# EyeSpark.net
KiCad netlist of a schematic drawn in EAGLE
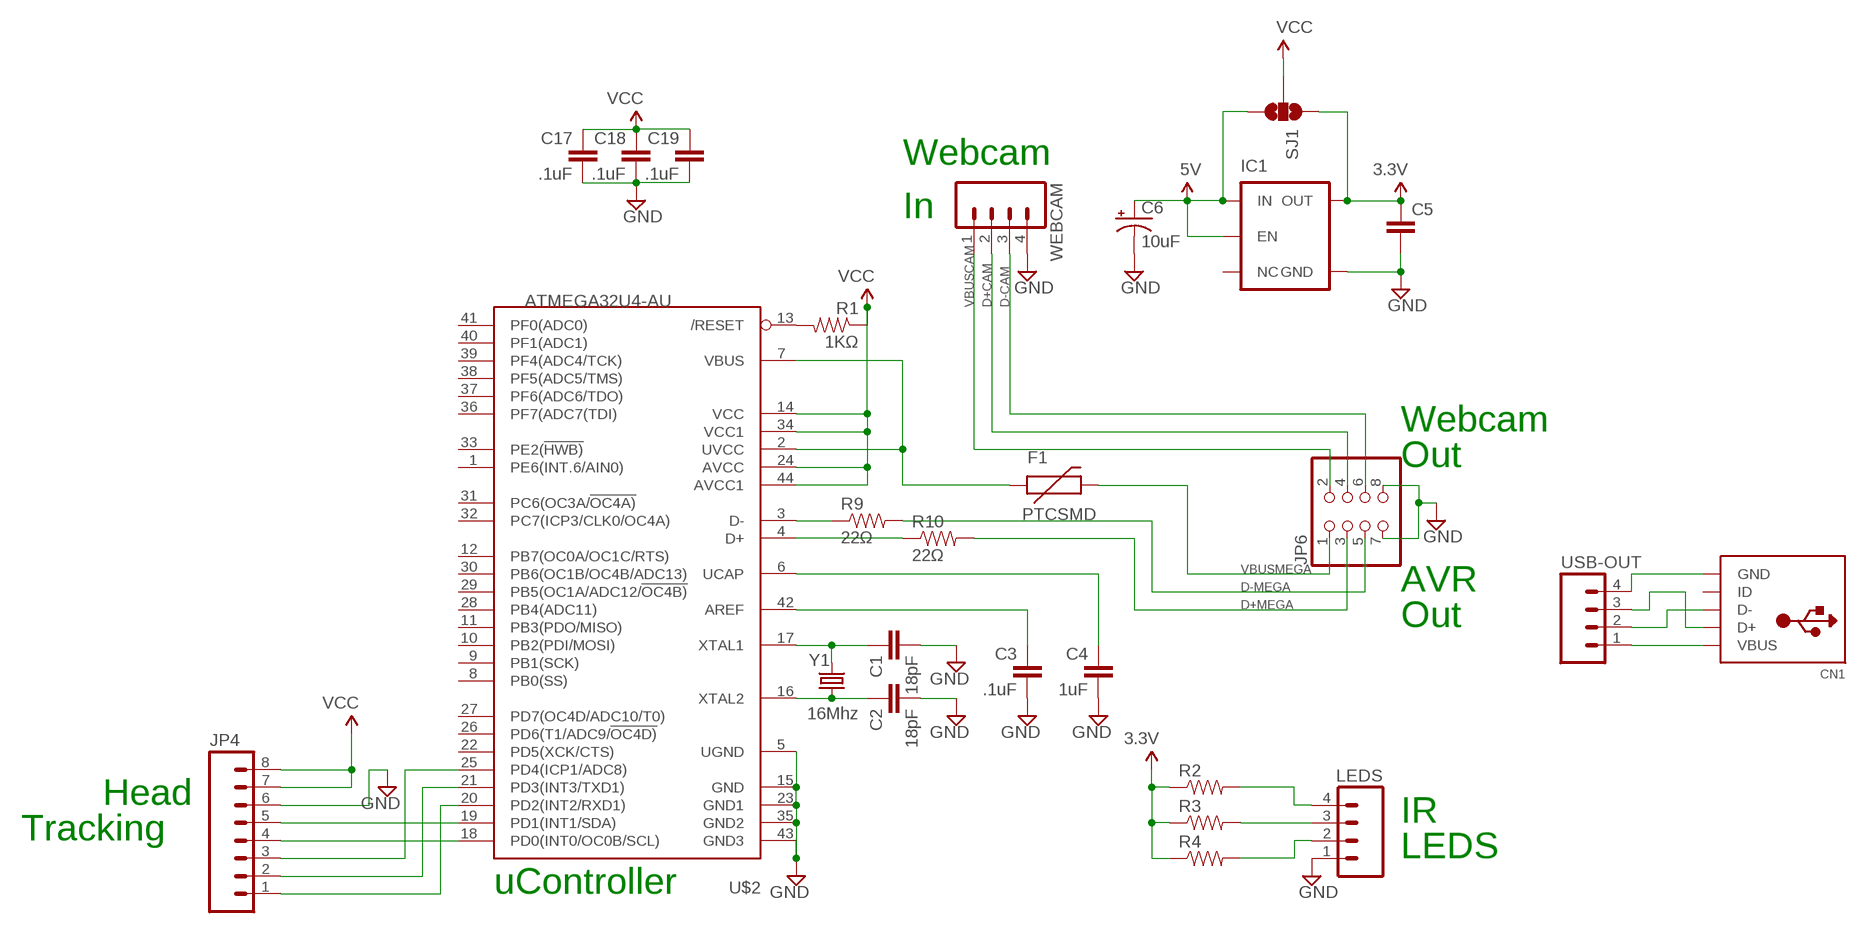
[diagram p0: schematic, sheet 1]

(export (version "E")
  (design (tool "Eeschema 10.0.6"))
  (components
    (comp (ref "C1")
      (value "18pF")
      (footprint "eagle-import:0805")
      (libsource (lib "eagle-import") (part "CAP0805"))
    )
    (comp (ref "C2")
      (value "18pF")
      (footprint "eagle-import:0805")
      (libsource (lib "eagle-import") (part "CAP0805"))
    )
    (comp (ref "C3")
      (value ".1uF")
      (footprint "eagle-import:0805")
      (libsource (lib "eagle-import") (part "CAP0805"))
    )
    (comp (ref "C4")
      (value "1uF")
      (footprint "eagle-import:0805")
      (libsource (lib "eagle-import") (part "CAP0805"))
    )
    (comp (ref "C5")
      (value "CAP0805")
      (footprint "eagle-import:0805")
      (libsource (lib "eagle-import") (part "CAP0805"))
    )
    (comp (ref "C6")
      (value "10uF")
      (footprint "eagle-import:EIA7343")
      (libsource (lib "eagle-import") (part "CAP_POL7343"))
    )
    (comp (ref "C17")
      (value ".1uF")
      (footprint "eagle-import:0805")
      (libsource (lib "eagle-import") (part "CAP0805"))
    )
    (comp (ref "C18")
      (value ".1uF")
      (footprint "eagle-import:0805")
      (libsource (lib "eagle-import") (part "CAP0805"))
    )
    (comp (ref "C19")
      (value ".1uF")
      (footprint "eagle-import:0805")
      (libsource (lib "eagle-import") (part "CAP0805"))
    )
    (comp (ref "CN1")
      (value "USBMINIB")
      (footprint "eagle-import:USB-MINIB")
      (libsource (lib "eagle-import") (part "USBMINIB"))
    )
    (comp (ref "F1")
      (value "PTCSMD")
      (footprint "eagle-import:PTC-1206")
      (libsource (lib "eagle-import") (part "PTCSMD"))
    )
    (comp (ref "IC1")
      (value "V_REG_TPS76433SOT23-5")
      (footprint "eagle-import:SOT23-5")
      (libsource (lib "eagle-import") (part "V_REG_TPS76433SOT23-5"))
    )
    (comp (ref "JP4")
      (value "M08LOCK")
      (footprint "eagle-import:1X08_LOCK")
      (libsource (lib "eagle-import") (part "M08LOCK"))
    )
    (comp (ref "JP6")
      (value "PINHD-2X4")
      (footprint "eagle-import:2X04")
      (libsource (lib "eagle-import") (part "PINHD-2X4"))
    )
    (comp (ref "LEDS")
      (value "M04PTH")
      (footprint "eagle-import:1X04")
      (libsource (lib "eagle-import") (part "M04PTH"))
    )
    (comp (ref "R1")
      (value "1KΩ")
      (footprint "eagle-import:0805")
      (libsource (lib "eagle-import") (part "RESISTOR0805-RES"))
    )
    (comp (ref "R2")
      (value "RESISTOR1206")
      (footprint "eagle-import:1206")
      (libsource (lib "eagle-import") (part "RESISTOR1206"))
    )
    (comp (ref "R3")
      (value "RESISTOR1206")
      (footprint "eagle-import:1206")
      (libsource (lib "eagle-import") (part "RESISTOR1206"))
    )
    (comp (ref "R4")
      (value "RESISTOR1206")
      (footprint "eagle-import:1206")
      (libsource (lib "eagle-import") (part "RESISTOR1206"))
    )
    (comp (ref "R9")
      (value "22Ω")
      (footprint "eagle-import:0805")
      (libsource (lib "eagle-import") (part "RESISTOR0805-RES"))
    )
    (comp (ref "R10")
      (value "22Ω")
      (footprint "eagle-import:0805")
      (libsource (lib "eagle-import") (part "RESISTOR0805-RES"))
    )
    (comp (ref "SJ1")
      (value "SOLDERJUMPER_2WAYT")
      (footprint "eagle-import:SJ_2")
      (libsource (lib "eagle-import") (part "SOLDERJUMPER_2WAYT"))
    )
    (comp (ref "U$2")
      (value "ATMEGA32U4-AU")
      (footprint "eagle-import:TQFP44")
      (libsource (lib "eagle-import") (part "ATMEGA32U4-AU"))
    )
    (comp (ref "USB-OUT")
      (value "M04PTH")
      (footprint "eagle-import:1X04")
      (libsource (lib "eagle-import") (part "M04PTH"))
    )
    (comp (ref "WEBCAM")
      (value "M04LOCK_LONGPADS")
      (footprint "eagle-import:1X04_LOCK_LONGPADS")
      (libsource (lib "eagle-import") (part "M04LOCK_LONGPADS"))
    )
    (comp (ref "Y1")
      (value "16Mhz")
      (footprint "eagle-import:CRYSTAL-SMD-5X3")
      (libsource (lib "eagle-import") (part "CRYSTAL5X3"))
    )
  )
  (nets
    (net (code "1") (name "/D+CAM") (class "Default")
      (node (ref "JP6") (pin "4") (pinfunction "4_4") (pintype "passive"))
      (node (ref "WEBCAM") (pin "2") (pinfunction "2_2") (pintype "passive"))
    )
    (net (code "2") (name "/D+MEGA") (class "Default")
      (node (ref "JP6") (pin "3") (pinfunction "3_3") (pintype "passive"))
      (node (ref "R10") (pin "2") (pinfunction "2_2") (pintype "passive"))
    )
    (net (code "3") (name "/D-CAM") (class "Default")
      (node (ref "JP6") (pin "6") (pinfunction "6_6") (pintype "passive"))
      (node (ref "WEBCAM") (pin "3") (pinfunction "3_3") (pintype "passive"))
    )
    (net (code "4") (name "/D-MEGA") (class "Default")
      (node (ref "JP6") (pin "5") (pinfunction "5_5") (pintype "passive"))
      (node (ref "R9") (pin "2") (pinfunction "2_2") (pintype "passive"))
    )
    (net (code "5") (name "/VBUSCAM") (class "Default")
      (node (ref "JP6") (pin "2") (pinfunction "2_2") (pintype "passive"))
      (node (ref "WEBCAM") (pin "1") (pinfunction "1_1") (pintype "passive"))
    )
    (net (code "6") (name "/VBUSMEGA") (class "Default")
      (node (ref "F1") (pin "2") (pinfunction "2_2") (pintype "bidirectional"))
      (node (ref "JP6") (pin "1") (pinfunction "1_1") (pintype "passive"))
    )
    (net (code "7") (name "3.3V") (class "Default")
      (node (ref "C5") (pin "1") (pinfunction "1_1") (pintype "passive"))
      (node (ref "IC1") (pin "5") (pinfunction "OUT_5") (pintype "passive"))
      (node (ref "R2") (pin "1") (pinfunction "1_1") (pintype "passive"))
      (node (ref "R3") (pin "1") (pinfunction "1_1") (pintype "passive"))
      (node (ref "R4") (pin "1") (pinfunction "1_1") (pintype "passive"))
      (node (ref "SJ1") (pin "1") (pinfunction "1_1") (pintype "passive"))
    )
    (net (code "8") (name "5V") (class "Default")
      (node (ref "C6") (pin "A") (pinfunction "+_A") (pintype "passive"))
      (node (ref "IC1") (pin "1") (pinfunction "IN_1") (pintype "input"))
      (node (ref "IC1") (pin "3") (pinfunction "EN_3") (pintype "input"))
      (node (ref "SJ1") (pin "3") (pinfunction "3_3") (pintype "passive"))
    )
    (net (code "9") (name "GND") (class "Default")
      (node (ref "C1") (pin "2") (pinfunction "2_2") (pintype "passive"))
      (node (ref "C17") (pin "2") (pinfunction "2_2") (pintype "passive"))
      (node (ref "C18") (pin "2") (pinfunction "2_2") (pintype "passive"))
      (node (ref "C19") (pin "2") (pinfunction "2_2") (pintype "passive"))
      (node (ref "C2") (pin "2") (pinfunction "2_2") (pintype "passive"))
      (node (ref "C3") (pin "2") (pinfunction "2_2") (pintype "passive"))
      (node (ref "C4") (pin "2") (pinfunction "2_2") (pintype "passive"))
      (node (ref "C5") (pin "2") (pinfunction "2_2") (pintype "passive"))
      (node (ref "C6") (pin "C") (pinfunction "-_C") (pintype "passive"))
      (node (ref "IC1") (pin "2") (pinfunction "GND_2") (pintype "input"))
      (node (ref "JP4") (pin "6") (pinfunction "6_6") (pintype "passive"))
      (node (ref "JP6") (pin "7") (pinfunction "7_7") (pintype "passive"))
      (node (ref "JP6") (pin "8") (pinfunction "8_8") (pintype "passive"))
      (node (ref "LEDS") (pin "1") (pinfunction "1_1") (pintype "passive"))
      (node (ref "U$2") (pin "15") (pinfunction "GND_15") (pintype "bidirectional"))
      (node (ref "U$2") (pin "23") (pinfunction "GND1_23") (pintype "bidirectional"))
      (node (ref "U$2") (pin "35") (pinfunction "GND2_35") (pintype "bidirectional"))
      (node (ref "U$2") (pin "43") (pinfunction "GND3_43") (pintype "bidirectional"))
      (node (ref "U$2") (pin "5") (pinfunction "UGND_5") (pintype "bidirectional"))
      (node (ref "WEBCAM") (pin "4") (pinfunction "4_4") (pintype "passive"))
    )
    (net (code "10") (name "Net-(CN1-PadD+)") (class "Default")
      (node (ref "CN1") (pin "D+") (pinfunction "D+_D+") (pintype "bidirectional"))
      (node (ref "USB-OUT") (pin "3") (pinfunction "3_3") (pintype "passive"))
    )
    (net (code "11") (name "Net-(CN1-PadD-)") (class "Default")
      (node (ref "CN1") (pin "D-") (pinfunction "D-_D-") (pintype "bidirectional"))
      (node (ref "USB-OUT") (pin "2") (pinfunction "2_2") (pintype "passive"))
    )
    (net (code "12") (name "Net-(CN1-PadGND)") (class "Default")
      (node (ref "CN1") (pin "GND") (pinfunction "GND_GND") (pintype "power_in"))
      (node (ref "USB-OUT") (pin "4") (pinfunction "4_4") (pintype "passive"))
    )
    (net (code "13") (name "Net-(CN1-PadVBUS)") (class "Default")
      (node (ref "CN1") (pin "VBUS") (pinfunction "VBUS_VBUS") (pintype "power_in"))
      (node (ref "USB-OUT") (pin "1") (pinfunction "1_1") (pintype "passive"))
    )
    (net (code "14") (name "Net-(LEDS-Pad2)") (class "Default")
      (node (ref "LEDS") (pin "2") (pinfunction "2_2") (pintype "passive"))
      (node (ref "R4") (pin "2") (pinfunction "2_2") (pintype "passive"))
    )
    (net (code "15") (name "Net-(LEDS-Pad3)") (class "Default")
      (node (ref "LEDS") (pin "3") (pinfunction "3_3") (pintype "passive"))
      (node (ref "R3") (pin "2") (pinfunction "2_2") (pintype "passive"))
    )
    (net (code "16") (name "Net-(LEDS-Pad4)") (class "Default")
      (node (ref "LEDS") (pin "4") (pinfunction "4_4") (pintype "passive"))
      (node (ref "R2") (pin "2") (pinfunction "2_2") (pintype "passive"))
    )
    (net (code "17") (name "Net-(U$2-AREF)") (class "Default")
      (node (ref "C3") (pin "1") (pinfunction "1_1") (pintype "passive"))
      (node (ref "U$2") (pin "42") (pinfunction "AREF_42") (pintype "bidirectional"))
    )
    (net (code "18") (name "Net-(U$2-D+)") (class "Default")
      (node (ref "R10") (pin "1") (pinfunction "1_1") (pintype "passive"))
      (node (ref "U$2") (pin "4") (pinfunction "D+_4") (pintype "bidirectional"))
    )
    (net (code "19") (name "Net-(U$2-D-)") (class "Default")
      (node (ref "R9") (pin "1") (pinfunction "1_1") (pintype "passive"))
      (node (ref "U$2") (pin "3") (pinfunction "D-_3") (pintype "bidirectional"))
    )
    (net (code "20") (name "Net-(U$2-PD0(INT0{slash}OC0B{slash}SCL))") (class "Default")
      (node (ref "JP4") (pin "4") (pinfunction "4_4") (pintype "passive"))
      (node (ref "U$2") (pin "18") (pinfunction "PD0(INT0/OC0B/SCL)_18") (pintype "bidirectional"))
    )
    (net (code "21") (name "Net-(U$2-PD1(INT1{slash}SDA))") (class "Default")
      (node (ref "JP4") (pin "5") (pinfunction "5_5") (pintype "passive"))
      (node (ref "U$2") (pin "19") (pinfunction "PD1(INT1/SDA)_19") (pintype "bidirectional"))
    )
    (net (code "22") (name "Net-(U$2-PD2(INT2{slash}RXD1))") (class "Default")
      (node (ref "JP4") (pin "1") (pinfunction "1_1") (pintype "passive"))
      (node (ref "U$2") (pin "20") (pinfunction "PD2(INT2/RXD1)_20") (pintype "bidirectional"))
    )
    (net (code "23") (name "Net-(U$2-PD3(INT3{slash}TXD1))") (class "Default")
      (node (ref "JP4") (pin "2") (pinfunction "2_2") (pintype "passive"))
      (node (ref "U$2") (pin "21") (pinfunction "PD3(INT3/TXD1)_21") (pintype "bidirectional"))
    )
    (net (code "24") (name "Net-(U$2-PD4(ICP1{slash}ADC8))") (class "Default")
      (node (ref "JP4") (pin "3") (pinfunction "3_3") (pintype "passive"))
      (node (ref "U$2") (pin "25") (pinfunction "PD4(ICP1/ADC8)_25") (pintype "bidirectional"))
    )
    (net (code "25") (name "Net-(U$2-UCAP)") (class "Default")
      (node (ref "C4") (pin "1") (pinfunction "1_1") (pintype "passive"))
      (node (ref "U$2") (pin "6") (pinfunction "UCAP_6") (pintype "bidirectional"))
    )
    (net (code "26") (name "Net-(U$2-UVCC)") (class "Default")
      (node (ref "F1") (pin "1") (pinfunction "1_1") (pintype "bidirectional"))
      (node (ref "U$2") (pin "2") (pinfunction "UVCC_2") (pintype "bidirectional"))
      (node (ref "U$2") (pin "7") (pinfunction "VBUS_7") (pintype "bidirectional"))
    )
    (net (code "27") (name "Net-(U$2-XTAL1)") (class "Default")
      (node (ref "C1") (pin "1") (pinfunction "1_1") (pintype "passive"))
      (node (ref "U$2") (pin "17") (pinfunction "XTAL1_17") (pintype "bidirectional"))
      (node (ref "Y1") (pin "1") (pinfunction "1_1") (pintype "passive"))
    )
    (net (code "28") (name "Net-(U$2-XTAL2)") (class "Default")
      (node (ref "C2") (pin "1") (pinfunction "1_1") (pintype "passive"))
      (node (ref "U$2") (pin "16") (pinfunction "XTAL2_16") (pintype "bidirectional"))
      (node (ref "Y1") (pin "3") (pinfunction "2_3") (pintype "passive"))
    )
    (net (code "29") (name "Net-(U$2-{slash}RESET)") (class "Default")
      (node (ref "R1") (pin "2") (pinfunction "2_2") (pintype "passive"))
      (node (ref "U$2") (pin "13") (pinfunction "/RESET_13") (pintype "bidirectional"))
    )
    (net (code "30") (name "VCC") (class "Default")
      (node (ref "C17") (pin "1") (pinfunction "1_1") (pintype "passive"))
      (node (ref "C18") (pin "1") (pinfunction "1_1") (pintype "passive"))
      (node (ref "C19") (pin "1") (pinfunction "1_1") (pintype "passive"))
      (node (ref "JP4") (pin "7") (pinfunction "7_7") (pintype "passive"))
      (node (ref "JP4") (pin "8") (pinfunction "8_8") (pintype "passive"))
      (node (ref "R1") (pin "1") (pinfunction "1_1") (pintype "passive"))
      (node (ref "SJ1") (pin "2") (pinfunction "2_2") (pintype "passive"))
      (node (ref "U$2") (pin "14") (pinfunction "VCC_14") (pintype "bidirectional"))
      (node (ref "U$2") (pin "24") (pinfunction "AVCC_24") (pintype "bidirectional"))
      (node (ref "U$2") (pin "34") (pinfunction "VCC1_34") (pintype "bidirectional"))
      (node (ref "U$2") (pin "44") (pinfunction "AVCC1_44") (pintype "bidirectional"))
    )
    (net (code "31") (name "unconnected-(CN1-PadID)") (class "Default")
      (node (ref "CN1") (pin "ID") (pinfunction "ID_ID") (pintype "bidirectional"))
    )
    (net (code "32") (name "unconnected-(IC1-NC-Pad4)") (class "Default")
      (node (ref "IC1") (pin "4") (pinfunction "NC_4") (pintype "input"))
    )
    (net (code "33") (name "unconnected-(U$2-PB0(SS)-Pad8)") (class "Default")
      (node (ref "U$2") (pin "8") (pinfunction "PB0(SS)_8") (pintype "bidirectional"))
    )
    (net (code "34") (name "unconnected-(U$2-PB1(SCK)-Pad9)") (class "Default")
      (node (ref "U$2") (pin "9") (pinfunction "PB1(SCK)_9") (pintype "bidirectional"))
    )
    (net (code "35") (name "unconnected-(U$2-PB2(PDI{slash}MOSI)-Pad10)") (class "Default")
      (node (ref "U$2") (pin "10") (pinfunction "PB2(PDI/MOSI)_10") (pintype "bidirectional"))
    )
    (net (code "36") (name "unconnected-(U$2-PB3(PDO{slash}MISO)-Pad11)") (class "Default")
      (node (ref "U$2") (pin "11") (pinfunction "PB3(PDO/MISO)_11") (pintype "bidirectional"))
    )
    (net (code "37") (name "unconnected-(U$2-PB4(ADC11)-Pad28)") (class "Default")
      (node (ref "U$2") (pin "28") (pinfunction "PB4(ADC11)_28") (pintype "bidirectional"))
    )
    (net (code "38") (name "unconnected-(U$2-PB5(OC1A{slash}ADC12{slash}~{OC4B})-Pad29)") (class "Default")
      (node (ref "U$2") (pin "29") (pinfunction "PB5(OC1A/ADC12/~{OC4B})_29") (pintype "bidirectional"))
    )
    (net (code "39") (name "unconnected-(U$2-PB6(OC1B{slash}OC4B{slash}ADC13)-Pad30)") (class "Default")
      (node (ref "U$2") (pin "30") (pinfunction "PB6(OC1B/OC4B/ADC13)_30") (pintype "bidirectional"))
    )
    (net (code "40") (name "unconnected-(U$2-PB7(OC0A{slash}OC1C{slash}RTS)-Pad12)") (class "Default")
      (node (ref "U$2") (pin "12") (pinfunction "PB7(OC0A/OC1C/RTS)_12") (pintype "bidirectional"))
    )
    (net (code "41") (name "unconnected-(U$2-PC6(OC3A{slash}~{OC4A})-Pad31)") (class "Default")
      (node (ref "U$2") (pin "31") (pinfunction "PC6(OC3A/~{OC4A})_31") (pintype "bidirectional"))
    )
    (net (code "42") (name "unconnected-(U$2-PC7(ICP3{slash}CLK0{slash}OC4A)-Pad32)") (class "Default")
      (node (ref "U$2") (pin "32") (pinfunction "PC7(ICP3/CLK0/OC4A)_32") (pintype "bidirectional"))
    )
    (net (code "43") (name "unconnected-(U$2-PD5(XCK{slash}CTS)-Pad22)") (class "Default")
      (node (ref "U$2") (pin "22") (pinfunction "PD5(XCK/CTS)_22") (pintype "bidirectional"))
    )
    (net (code "44") (name "unconnected-(U$2-PD6(T1{slash}ADC9{slash}~{OC4D})-Pad26)") (class "Default")
      (node (ref "U$2") (pin "26") (pinfunction "PD6(T1/ADC9/~{OC4D})_26") (pintype "bidirectional"))
    )
    (net (code "45") (name "unconnected-(U$2-PD7(OC4D{slash}ADC10{slash}T0)-Pad27)") (class "Default")
      (node (ref "U$2") (pin "27") (pinfunction "PD7(OC4D/ADC10/T0)_27") (pintype "bidirectional"))
    )
    (net (code "46") (name "unconnected-(U$2-PE2(~{HWB})-Pad33)") (class "Default")
      (node (ref "U$2") (pin "33") (pinfunction "PE2(~{HWB})_33") (pintype "bidirectional"))
    )
    (net (code "47") (name "unconnected-(U$2-PE6(INT.6{slash}AIN0)-Pad1)") (class "Default")
      (node (ref "U$2") (pin "1") (pinfunction "PE6(INT.6/AIN0)_1") (pintype "bidirectional"))
    )
    (net (code "48") (name "unconnected-(U$2-PF0(ADC0)-Pad41)") (class "Default")
      (node (ref "U$2") (pin "41") (pinfunction "PF0(ADC0)_41") (pintype "bidirectional"))
    )
    (net (code "49") (name "unconnected-(U$2-PF1(ADC1)-Pad40)") (class "Default")
      (node (ref "U$2") (pin "40") (pinfunction "PF1(ADC1)_40") (pintype "bidirectional"))
    )
    (net (code "50") (name "unconnected-(U$2-PF4(ADC4{slash}TCK)-Pad39)") (class "Default")
      (node (ref "U$2") (pin "39") (pinfunction "PF4(ADC4/TCK)_39") (pintype "bidirectional"))
    )
    (net (code "51") (name "unconnected-(U$2-PF5(ADC5{slash}TMS)-Pad38)") (class "Default")
      (node (ref "U$2") (pin "38") (pinfunction "PF5(ADC5/TMS)_38") (pintype "bidirectional"))
    )
    (net (code "52") (name "unconnected-(U$2-PF6(ADC6{slash}TDO)-Pad37)") (class "Default")
      (node (ref "U$2") (pin "37") (pinfunction "PF6(ADC6/TDO)_37") (pintype "bidirectional"))
    )
    (net (code "53") (name "unconnected-(U$2-PF7(ADC7(TDI)-Pad36)") (class "Default")
      (node (ref "U$2") (pin "36") (pinfunction "PF7(ADC7(TDI)_36") (pintype "bidirectional"))
    )
  )
)
